# TWIST_SWITCHv1_1.net
KiCad netlist of a schematic drawn in Altium Designer
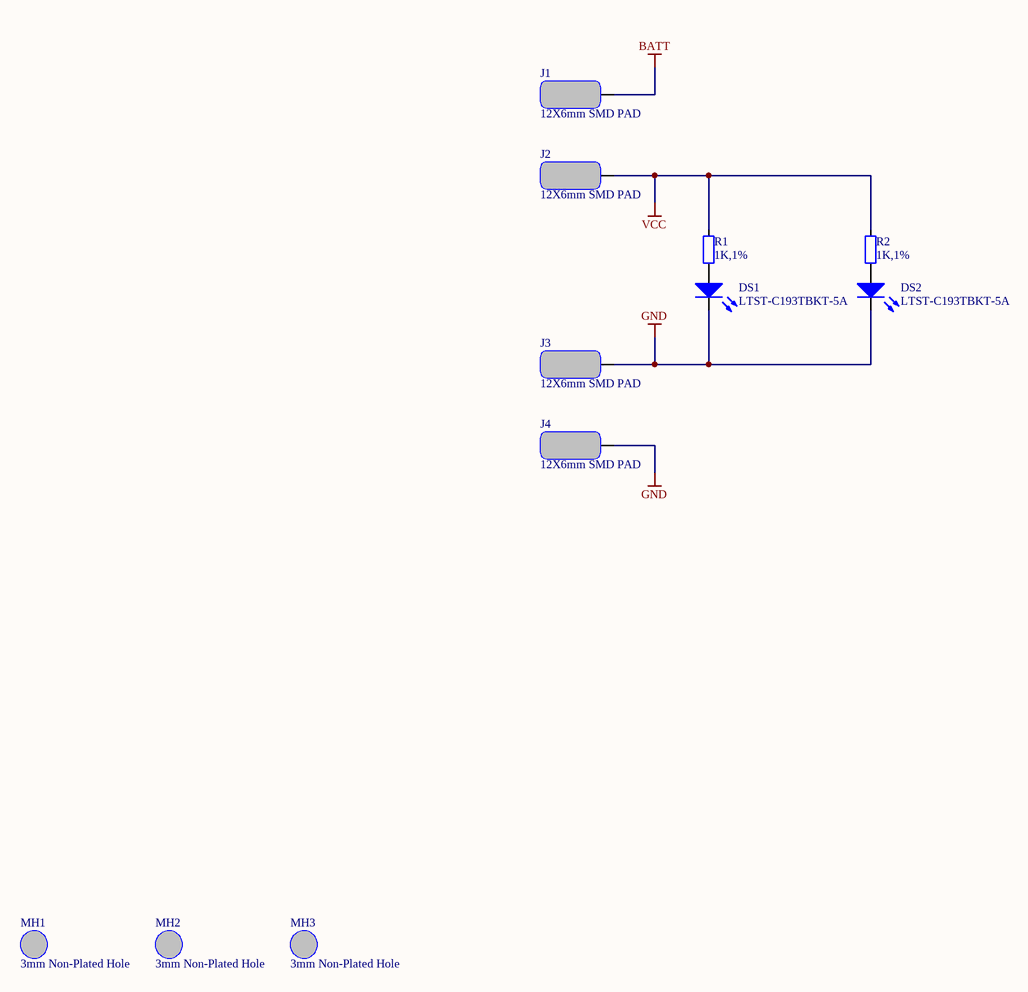
[diagram p0: TWIST_SWITCHv1.1.SchDoc]

(export (version "E")
  (design (tool "Eeschema 10.0.6"))
  (components
    (comp (ref "DS1")
      (value "LTST-C193TBKT-5A")
      (footprint "LED_SML-LX0603")
      (description "LED 0603 SM Blue")
      (fields (field (name "MANUFACTURER") "Lite-On Inc"))
      (libsource (lib "library") (part "LED_1"))
    )
    (comp (ref "DS2")
      (value "LTST-C193TBKT-5A")
      (footprint "LED_SML-LX0603")
      (description "LED 0603 SM Blue")
      (fields (field (name "MANUFACTURER") "Lite-On Inc"))
      (libsource (lib "library") (part "LED_1"))
    )
    (comp (ref "J1")
      (value "12X6mm SMD PAD")
      (footprint "PAD-SM_12x6MM")
      (libsource (lib "library") (part "SMD_PAD"))
    )
    (comp (ref "J2")
      (value "12X6mm SMD PAD")
      (footprint "PAD-SM_12x6MM")
      (libsource (lib "library") (part "SMD_PAD"))
    )
    (comp (ref "J3")
      (value "12X6mm SMD PAD")
      (footprint "PAD-SM_12x6MM")
      (libsource (lib "library") (part "SMD_PAD"))
    )
    (comp (ref "J4")
      (value "12X6mm SMD PAD")
      (footprint "PAD-SM_12x6MM")
      (libsource (lib "library") (part "SMD_PAD"))
    )
    (comp (ref "MH1")
      (value "3mm Non-Plated Hole")
      (footprint "MTG310X600")
      (libsource (lib "library") (part "HOLE_UNPLATED"))
    )
    (comp (ref "MH2")
      (value "3mm Non-Plated Hole")
      (footprint "MTG310X600")
      (libsource (lib "library") (part "HOLE_UNPLATED"))
    )
    (comp (ref "MH3")
      (value "3mm Non-Plated Hole")
      (footprint "MTG310X600")
      (libsource (lib "library") (part "HOLE_UNPLATED"))
    )
    (comp (ref "R1")
      (value "1K,1%")
      (footprint "RESC1005X04N_0402")
      (description "RES 1K 1/16W 1% 0402")
      (fields (field (name "MANUFACTURER") "Yageo") (field (name "POWER") "0.0625W"))
      (libsource (lib "library") (part "RESISTOR_1"))
    )
    (comp (ref "R2")
      (value "1K,1%")
      (footprint "RESC1005X04N_0402")
      (description "RES 1K 1/16W 1% 0402")
      (fields (field (name "MANUFACTURER") "Yageo") (field (name "POWER") "0.0625W"))
      (libsource (lib "library") (part "RESISTOR_1"))
    )
  )
  (nets
    (net (code "1") (name "BATT") (class "Default") (node (ref "J1") (pin "1") (pintype "passive")))
    (net (code "2") (name "GND") (class "Default")
      (node (ref "DS1") (pin "1") (pinfunction "C_1") (pintype "passive"))
      (node (ref "DS2") (pin "1") (pinfunction "C_1") (pintype "passive"))
      (node (ref "J3") (pin "1") (pintype "passive"))
      (node (ref "J4") (pin "1") (pintype "passive"))
    )
    (net (code "3") (name "Net-(DS1-A)") (class "Default")
      (node (ref "DS1") (pin "2") (pinfunction "A_2") (pintype "passive"))
      (node (ref "R1") (pin "2") (pinfunction "2_2") (pintype "passive"))
    )
    (net (code "4") (name "Net-(DS2-A)") (class "Default")
      (node (ref "DS2") (pin "2") (pinfunction "A_2") (pintype "passive"))
      (node (ref "R2") (pin "2") (pinfunction "2_2") (pintype "passive"))
    )
    (net (code "5") (name "VCC") (class "Default")
      (node (ref "J2") (pin "1") (pintype "passive"))
      (node (ref "R1") (pin "1") (pinfunction "1_1") (pintype "passive"))
      (node (ref "R2") (pin "1") (pinfunction "1_1") (pintype "passive"))
    )
  )
)
